# Esquematico.net
KiCad netlist of a schematic drawn in Altium Designer
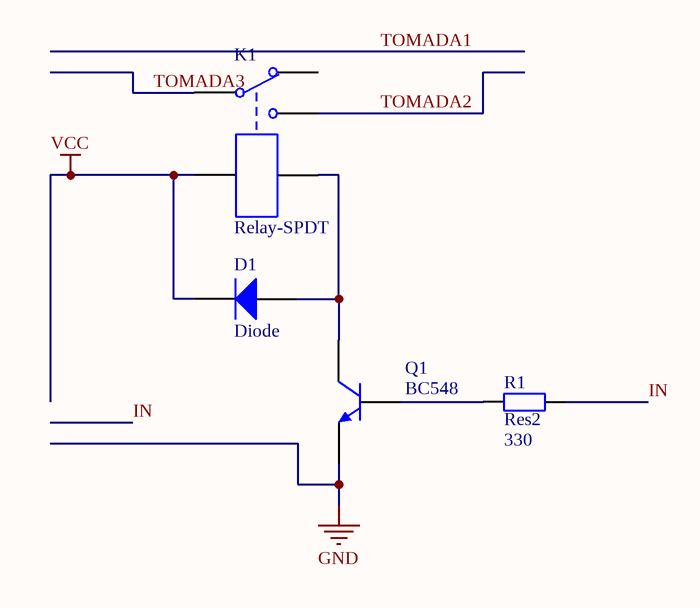
[diagram p0: Esquematico.SchDoc]

(export (version "E")
  (design (tool "Eeschema 10.0.6"))
  (components
    (comp (ref "D1")
      (value "Diode")
      (footprint "DO-35")
      (description "Default Diode")
      (fields (field (name "PUBLISHER") "Altium Limited"))
      (libsource (lib "Components") (part "Diode"))
    )
    (comp (ref "K1")
      (value "Relay-SPDT")
      (footprint "relay")
      (description "Single-Pole Dual-Throw Relay")
      (fields (field (name "PUBLISHER") "Altium Limited"))
      (libsource (lib "Miscellaneous Devices") (part "Relay-SPDT"))
    )
    (comp (ref "Q1")
      (value "BC548")
      (footprint "TO-92")
      (description "NPN General Purpose Amplifier")
      (fields (field (name "PUBLISHER") "Altium Limited"))
      (libsource (lib "Components") (part "BC548"))
    )
    (comp (ref "R1")
      (value "Res2")
      (footprint "AXIAL-0.4")
      (description "Resistor")
      (fields (field (name "ALTIUM_VALUE") "330") (field (name "PUBLISHER") "Altium Limited"))
      (libsource (lib "Components") (part "Res2"))
    )
  )
  (nets
    (net (code "1") (name "/IN") (class "Default")
      (node (ref "R1") (pin "2") (pinfunction "2_2") (pintype "passive"))
    )
    (net (code "3") (name "/TOMADA2") (class "Default")
      (node (ref "K1") (pin "3") (pinfunction "3_3") (pintype "passive"))
    )
    (net (code "4") (name "/TOMADA3") (class "Default")
      (node (ref "K1") (pin "1") (pinfunction "1_1") (pintype "passive"))
    )
    (net (code "5") (name "GND") (class "Default")
      (node (ref "Q1") (pin "1") (pinfunction "E_1") (pintype "passive"))
    )
    (net (code "6") (name "Net-(D1-A)") (class "Default")
      (node (ref "D1") (pin "1") (pinfunction "A_1") (pintype "passive"))
      (node (ref "K1") (pin "5") (pinfunction "5_5") (pintype "passive"))
      (node (ref "Q1") (pin "3") (pinfunction "C_3") (pintype "passive"))
    )
    (net (code "7") (name "Net-(Q1-B)") (class "Default")
      (node (ref "Q1") (pin "2") (pinfunction "B_2") (pintype "passive"))
      (node (ref "R1") (pin "1") (pinfunction "1_1") (pintype "passive"))
    )
    (net (code "8") (name "VCC") (class "Default")
      (node (ref "D1") (pin "2") (pinfunction "K_2") (pintype "passive"))
      (node (ref "K1") (pin "4") (pinfunction "4_4") (pintype "passive"))
    )
    (net (code "9") (name "unconnected-(K1-Pad2)") (class "Default")
      (node (ref "K1") (pin "2") (pinfunction "2_2") (pintype "passive"))
    )
  )
)
